# KHOI_NGUON.net
KiCad netlist of a schematic drawn in Altium Designer
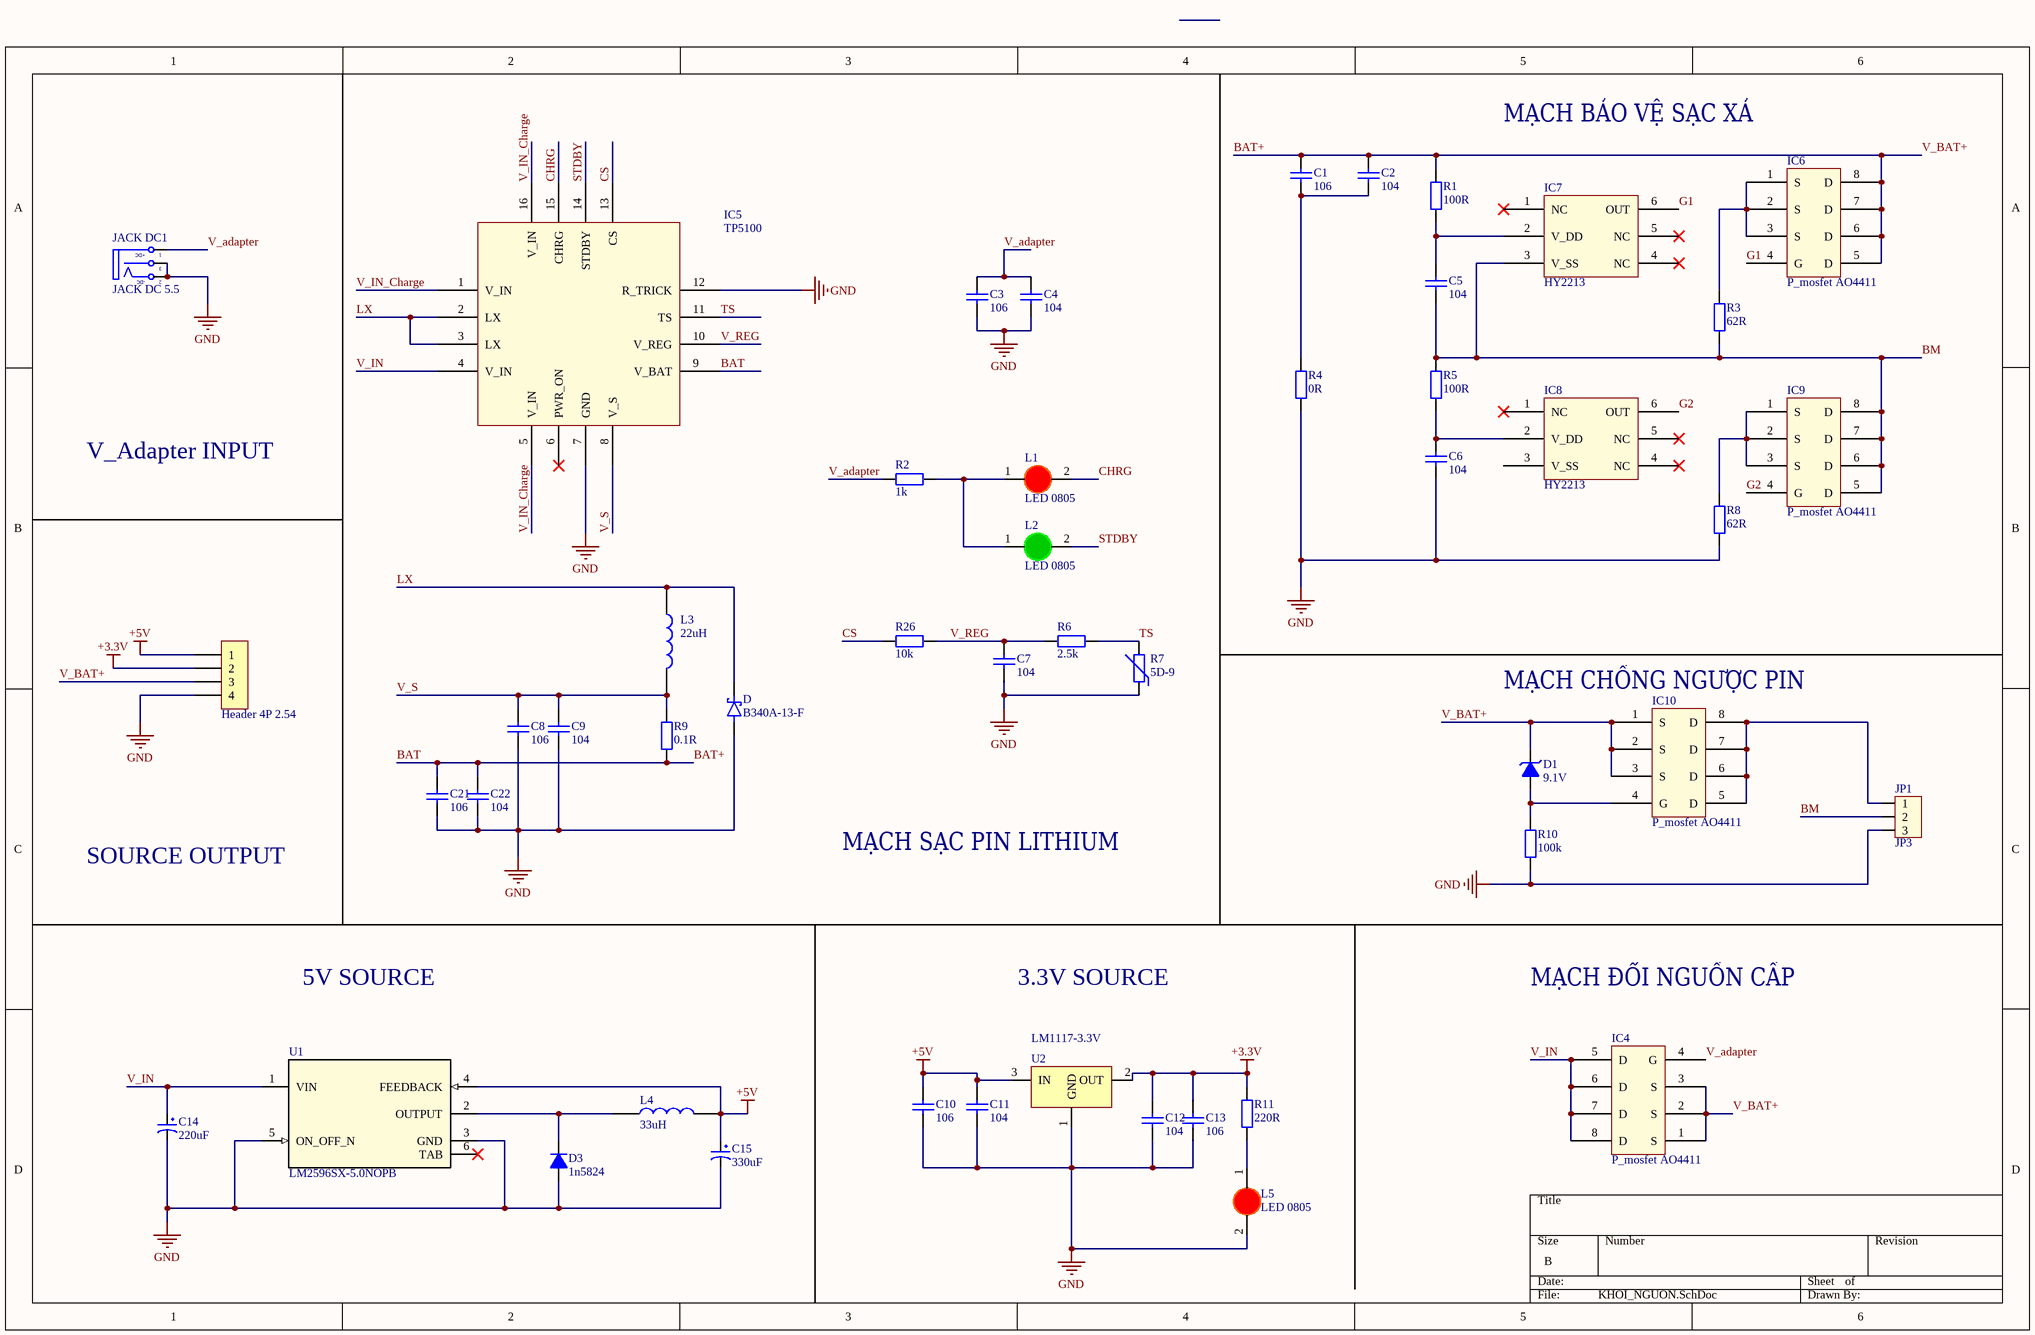
[diagram p0: KHOI_NGUON.SchDoc]

(export (version "E")
  (design (tool "Eeschema 10.0.6"))
  (components
    (comp (ref "C1")
      (value "106")
      (footprint "tu 1206")
      (description "Dán")
      (libsource (lib "Altium_Lib_by_KhueNguyenCreator") (part "Tu 1206 106 16V 20%"))
    )
    (comp (ref "C2")
      (value "104")
      (footprint "tu 1206")
      (description "Dán")
      (libsource (lib "Altium_Lib_by_KhueNguyenCreator") (part "Tu 1206 104 50V 20%"))
    )
    (comp (ref "C3")
      (value "106")
      (footprint "tu 1206")
      (description "Dán")
      (libsource (lib "Altium_Lib_by_KhueNguyenCreator") (part "Tu 1206 106 16V 20%"))
    )
    (comp (ref "C4")
      (value "104")
      (footprint "tu 1206")
      (description "Dán")
      (libsource (lib "Altium_Lib_by_KhueNguyenCreator") (part "Tu 1206 104 50V 20%"))
    )
    (comp (ref "C5")
      (value "104")
      (footprint "tu 1206")
      (description "Dán")
      (libsource (lib "Altium_Lib_by_KhueNguyenCreator") (part "Tu 1206 104 50V 20%"))
    )
    (comp (ref "C6")
      (value "104")
      (footprint "tu 1206")
      (description "Dán")
      (libsource (lib "Altium_Lib_by_KhueNguyenCreator") (part "Tu 1206 104 50V 20%"))
    )
    (comp (ref "C7")
      (value "104")
      (footprint "tu 1206")
      (description "Dán")
      (libsource (lib "Altium_Lib_by_KhueNguyenCreator") (part "Tu 1206 104 50V 20%"))
    )
    (comp (ref "C8")
      (value "106")
      (footprint "tu 1206")
      (description "Dán")
      (libsource (lib "Altium_Lib_by_KhueNguyenCreator") (part "Tu 1206 106 16V 20%"))
    )
    (comp (ref "C9")
      (value "104")
      (footprint "tu 1206")
      (description "Dán")
      (libsource (lib "Altium_Lib_by_KhueNguyenCreator") (part "Tu 1206 104 50V 20%"))
    )
    (comp (ref "C10")
      (value "106")
      (footprint "tu 1206")
      (description "Dán")
      (libsource (lib "Altium_Lib_by_KhueNguyenCreator") (part "Tu 1206 106 16V 20%"))
    )
    (comp (ref "C11")
      (value "104")
      (footprint "tu 1206")
      (description "Dán")
      (libsource (lib "Altium_Lib_by_KhueNguyenCreator") (part "Tu 1206 104 50V 20%"))
    )
    (comp (ref "C12")
      (value "104")
      (footprint "tu 1206")
      (description "Dán")
      (libsource (lib "Altium_Lib_by_KhueNguyenCreator") (part "Tu 1206 104 50V 20%"))
    )
    (comp (ref "C13")
      (value "106")
      (footprint "tu 1206")
      (description "Dán")
      (libsource (lib "Altium_Lib_by_KhueNguyenCreator") (part "Tu 1206 106 16V 20%"))
    )
    (comp (ref "C14")
      (value "220uF")
      (footprint "tu hoa 6.5mm")
      (description "Cắm")
      (libsource (lib "Altium_Lib_by_KhueNguyenCreator") (part "Tu Hoa 220uF 16V 7x11"))
    )
    (comp (ref "C15")
      (value "330uF")
      (footprint "tu hoa 10mm")
      (description "Cắm")
      (libsource (lib "Altium_Lib_by_KhueNguyenCreator") (part "Tu Hoa 330uF 35V 10x12"))
    )
    (comp (ref "C21")
      (value "106")
      (footprint "tu 1206")
      (description "Dán")
      (libsource (lib "Altium_Lib_by_KhueNguyenCreator") (part "Tu 1206 106 16V 20%"))
    )
    (comp (ref "C22")
      (value "104")
      (footprint "tu 1206")
      (description "Dán")
      (libsource (lib "Altium_Lib_by_KhueNguyenCreator") (part "Tu 1206 104 50V 20%"))
    )
    (comp (ref "D")
      (value "B340A-13-F")
      (footprint "DIOM5226X240N")
      (description "Diode Schottky 40V 3A Surface Mount SMA")
      (fields (field (name "MF") "Diodes Inc."))
      (libsource (lib "Altium_Lib_by_KhueNguyenCreator") (part "B340A-13-F"))
    )
    (comp (ref "D1")
      (value "9.1V")
      (footprint "DIODE ZENNER SMD SOD80")
      (description "Dán")
      (libsource (lib "Altium_Lib_by_KhueNguyenCreator") (part "Diode Zener 9.1V"))
    )
    (comp (ref "D3")
      (value "1n5824")
      (footprint "DIODE 1A")
      (description "Cắm")
      (libsource (lib "Altium_Lib_by_KhueNguyenCreator") (part "Diode 1N4007"))
    )
    (comp (ref "H1")
      (value "Header 4P 2.54")
      (footprint "XH2.54M-4")
      (description "Cắm")
      (libsource (lib "Altium_Lib_by_KhueNguyenCreator") (part "Header 4P 2.54 Duc Thang"))
    )
    (comp (ref "IC4")
      (value "P_mosfet AO4411")
      (footprint "SOIC8_AO4411")
      (libsource (lib "") (part "P_mosfet AO4411_1"))
    )
    (comp (ref "IC5")
      (value "TP5100")
      (footprint "QFN_16_4*4")
      (description "IC sạc pin Lithium")
      (libsource (lib "Schlib1") (part "TP5100"))
    )
    (comp (ref "IC6")
      (value "P_mosfet AO4411")
      (footprint "SOIC8_AO4411")
      (libsource (lib "AO4411") (part "P_mosfet AO4411"))
    )
    (comp (ref "IC7")
      (value "HY2213")
      (footprint "SOT_23_6_HY2213")
      (libsource (lib "HY22213") (part "HY2213"))
    )
    (comp (ref "IC8")
      (value "HY2213")
      (footprint "SOT_23_6_HY2213")
      (libsource (lib "HY22213") (part "HY2213"))
    )
    (comp (ref "IC9")
      (value "P_mosfet AO4411")
      (footprint "SOIC8_AO4411")
      (libsource (lib "AO4411") (part "P_mosfet AO4411"))
    )
    (comp (ref "IC10")
      (value "P_mosfet AO4411")
      (footprint "SOIC8_AO4411")
      (libsource (lib "AO4411") (part "P_mosfet AO4411"))
    )
    (comp (ref "JACK DC1")
      (value "JACK DC 5.5")
      (footprint "JACK DC 5.5")
      (libsource (lib "Altium_Lib_by_KhueNguyenCreator") (part "JACK DC 5.5"))
    )
    (comp (ref "JP1")
      (value "JP3")
      (footprint "CON3")
      (description "Connector 3")
      (libsource (lib "My library altium") (part "Con3"))
    )
    (comp (ref "L1")
      (value "LED 0805")
      (footprint "LED-1206-Red")
      (description "Dán")
      (libsource (lib "Altium_Lib_by_KhueNguyenCreator") (part "LED 1206 Do"))
    )
    (comp (ref "L2")
      (value "LED 0805")
      (footprint "LED-1206-Green")
      (description "Dán")
      (libsource (lib "Altium_Lib_by_KhueNguyenCreator") (part "LED 1206 Xanh La"))
    )
    (comp (ref "L3")
      (value "22uH")
      (footprint "Cuon Cam 12x12x10")
      (description "Dán")
      (libsource (lib "Altium_Lib_by_KhueNguyenCreator") (part "CUON CAM 100uH SMD"))
    )
    (comp (ref "L4")
      (value "33uH")
      (footprint "Cuon Cam 12x12x10")
      (description "Dán")
      (libsource (lib "") (part "CUON CAM 100uH SMD_1"))
    )
    (comp (ref "L5")
      (value "LED 0805")
      (footprint "LED-0805-Red")
      (description "Dán")
      (libsource (lib "Altium_Lib_by_KhueNguyenCreator") (part "LED 0805 Do"))
    )
    (comp (ref "R1")
      (value "100R")
      (footprint "tro smd 0805")
      (description "Dán")
      (libsource (lib "Altium_Lib_by_KhueNguyenCreator") (part "Tro 0805 1% 10R"))
    )
    (comp (ref "R2")
      (value "1k")
      (footprint "tro smd 0805")
      (description "Dán")
      (libsource (lib "Altium_Lib_by_KhueNguyenCreator") (part "Tro 0805 1% 1k"))
    )
    (comp (ref "R3")
      (value "62R")
      (footprint "tro smd 0805")
      (description "Dán")
      (libsource (lib "Altium_Lib_by_KhueNguyenCreator") (part "Tro 0805 5% 62R"))
    )
    (comp (ref "R4")
      (value "0R")
      (footprint "tro smd 0805")
      (description "Dán")
      (libsource (lib "Altium_Lib_by_KhueNguyenCreator") (part "Tro 0805 5% 0R"))
    )
    (comp (ref "R5")
      (value "100R")
      (footprint "tro smd 0805")
      (description "Dán")
      (libsource (lib "Altium_Lib_by_KhueNguyenCreator") (part "Tro 0805 1% 10R"))
    )
    (comp (ref "R6")
      (value "2.5k")
      (footprint "tro smd 0805")
      (description "Dán")
      (libsource (lib "Altium_Lib_by_KhueNguyenCreator") (part "Tro 0805 5% 2.7k"))
    )
    (comp (ref "R7")
      (value "5D-9")
      (footprint "tro nhiet d-9")
      (description "Cắm")
      (libsource (lib "Altium_Lib_by_KhueNguyenCreator") (part "Tro Nhiet NTC 5D-9"))
    )
    (comp (ref "R8")
      (value "62R")
      (footprint "tro smd 0805")
      (description "Dán")
      (libsource (lib "Altium_Lib_by_KhueNguyenCreator") (part "Tro 0805 5% 62R"))
    )
    (comp (ref "R9")
      (value "0.1R")
      (footprint "tro smd 2512")
      (description "Dán")
      (libsource (lib "Altium_Lib_by_KhueNguyenCreator") (part "Tro 2512 5% 0.1R"))
    )
    (comp (ref "R10")
      (value "100k")
      (footprint "tro smd 0805")
      (description "Dán")
      (libsource (lib "Altium_Lib_by_KhueNguyenCreator") (part "Tro 0805 5% 100k"))
    )
    (comp (ref "R11")
      (value "220R")
      (footprint "tro smd 0805")
      (description "Dán")
      (libsource (lib "Altium_Lib_by_KhueNguyenCreator") (part "Tro 0805 1% 0.5R"))
    )
    (comp (ref "R26")
      (value "10k")
      (footprint "tro smd 0805")
      (description "Dán")
      (libsource (lib "Altium_Lib_by_KhueNguyenCreator") (part "Tro 0805 1% 1k"))
    )
    (comp (ref "U1")
      (value "LM2596SX-5.0NOPB")
      (footprint "KTT0005B")
      (description "No Description Available")
      (fields
        (field (name "PARTNUMBER") "LM2596SX-ADJ/NOPB")
        (field (name "ALTERNATE_PARTNUMBER") "LM2596S-ADJ/NOPB")
      )
      (libsource (lib "LM2596SX-5P0NOPB") (part "LM2596SX-5.0NOPB"))
    )
    (comp (ref "U2")
      (value "LM1117-3.3V")
      (footprint "LM1117-SOP")
      (description "800mA Low-Dropout Linear Regulator")
      (fields (field (name "CREATOR") "Nguyen Ba Bien"))
      (libsource (lib "My library altium") (part "LM1117"))
    )
  )
  (nets
    (net (code "1") (name "+3.3V") (class "Default")
      (node (ref "C12") (pin "1") (pinfunction "1_1") (pintype "passive"))
      (node (ref "C13") (pin "2") (pinfunction "2_2") (pintype "passive"))
      (node (ref "H1") (pin "2") (pinfunction "2_2") (pintype "passive"))
      (node (ref "R11") (pin "1") (pinfunction "1_1") (pintype "passive"))
      (node (ref "U2") (pin "2") (pinfunction "OUT_2") (pintype "passive"))
    )
    (net (code "2") (name "+5V") (class "Default")
      (node (ref "C10") (pin "2") (pinfunction "2_2") (pintype "passive"))
      (node (ref "C11") (pin "1") (pinfunction "1_1") (pintype "passive"))
      (node (ref "C15") (pin "1") (pinfunction "1_1") (pintype "passive"))
      (node (ref "H1") (pin "1") (pinfunction "1_1") (pintype "passive"))
      (node (ref "L4") (pin "2") (pinfunction "2_2") (pintype "passive"))
      (node (ref "U1") (pin "4") (pinfunction "FEEDBACK_4") (pintype "input"))
      (node (ref "U2") (pin "3") (pinfunction "IN_3") (pintype "passive"))
    )
    (net (code "3") (name "/BAT") (class "Default")
      (node (ref "C1") (pin "2") (pinfunction "2_2") (pintype "passive"))
      (node (ref "C2") (pin "1") (pinfunction "1_1") (pintype "passive"))
      (node (ref "C21") (pin "2") (pinfunction "2_2") (pintype "passive"))
      (node (ref "C22") (pin "1") (pinfunction "1_1") (pintype "passive"))
      (node (ref "D1") (pin "2") (pinfunction "K_2") (pintype "passive"))
      (node (ref "H1") (pin "3") (pinfunction "3_3") (pintype "passive"))
      (node (ref "IC10") (pin "1") (pinfunction "S_1") (pintype "passive"))
      (node (ref "IC10") (pin "2") (pinfunction "S_2") (pintype "passive"))
      (node (ref "IC10") (pin "3") (pinfunction "S_3") (pintype "passive"))
      (node (ref "IC4") (pin "1") (pinfunction "S_1") (pintype "passive"))
      (node (ref "IC4") (pin "2") (pinfunction "S_2") (pintype "passive"))
      (node (ref "IC4") (pin "3") (pinfunction "S_3") (pintype "passive"))
      (node (ref "IC5") (pin "9") (pinfunction "V_BAT_9") (pintype "passive"))
      (node (ref "IC6") (pin "5") (pinfunction "D_5") (pintype "passive"))
      (node (ref "IC6") (pin "6") (pinfunction "D_6") (pintype "passive"))
      (node (ref "IC6") (pin "7") (pinfunction "D_7") (pintype "passive"))
      (node (ref "IC6") (pin "8") (pinfunction "D_8") (pintype "passive"))
      (node (ref "R1") (pin "2") (pinfunction "2_2") (pintype "passive"))
      (node (ref "R9") (pin "1") (pinfunction "1_1") (pintype "passive"))
    )
    (net (code "4") (name "/BM") (class "Default")
      (node (ref "C5") (pin "2") (pinfunction "2_2") (pintype "passive"))
      (node (ref "IC7") (pin "3") (pinfunction "V_SS_3") (pintype "passive"))
      (node (ref "IC9") (pin "5") (pinfunction "D_5") (pintype "passive"))
      (node (ref "IC9") (pin "6") (pinfunction "D_6") (pintype "passive"))
      (node (ref "IC9") (pin "7") (pinfunction "D_7") (pintype "passive"))
      (node (ref "IC9") (pin "8") (pinfunction "D_8") (pintype "passive"))
      (node (ref "JP1") (pin "2") (pinfunction "2_2") (pintype "passive"))
      (node (ref "R3") (pin "1") (pinfunction "1_1") (pintype "passive"))
      (node (ref "R5") (pin "2") (pinfunction "2_2") (pintype "passive"))
    )
    (net (code "5") (name "/CHRG") (class "Default")
      (node (ref "IC5") (pin "15") (pinfunction "CHRG_15") (pintype "passive"))
      (node (ref "L1") (pin "2") (pinfunction "K_2") (pintype "passive"))
    )
    (net (code "6") (name "/CS") (class "Default")
      (node (ref "IC5") (pin "13") (pinfunction "CS_13") (pintype "passive"))
      (node (ref "R26") (pin "2") (pinfunction "2_2") (pintype "passive"))
    )
    (net (code "7") (name "/G1") (class "Default")
      (node (ref "IC6") (pin "4") (pinfunction "G_4") (pintype "passive"))
      (node (ref "IC7") (pin "6") (pinfunction "OUT_6") (pintype "passive"))
    )
    (net (code "8") (name "/G2") (class "Default")
      (node (ref "IC8") (pin "6") (pinfunction "OUT_6") (pintype "passive"))
      (node (ref "IC9") (pin "4") (pinfunction "G_4") (pintype "passive"))
    )
    (net (code "9") (name "/LX") (class "Default")
      (node (ref "D") (pin "C") (pinfunction "C_C") (pintype "passive"))
      (node (ref "IC5") (pin "2") (pinfunction "LX_2") (pintype "passive"))
      (node (ref "IC5") (pin "3") (pinfunction "LX_3") (pintype "passive"))
      (node (ref "L3") (pin "1") (pinfunction "1_1") (pintype "passive"))
    )
    (net (code "10") (name "/STDBY") (class "Default")
      (node (ref "IC5") (pin "14") (pinfunction "STDBY_14") (pintype "passive"))
      (node (ref "L2") (pin "2") (pinfunction "K_2") (pintype "passive"))
    )
    (net (code "11") (name "/TS") (class "Default")
      (node (ref "IC5") (pin "11") (pinfunction "TS_11") (pintype "passive"))
      (node (ref "R6") (pin "2") (pinfunction "2_2") (pintype "passive"))
      (node (ref "R7") (pin "2") (pinfunction "2_2") (pintype "passive"))
    )
    (net (code "12") (name "/V_IN") (class "Default")
      (node (ref "C14") (pin "1") (pinfunction "1_1") (pintype "passive"))
      (node (ref "IC4") (pin "5") (pinfunction "D_5") (pintype "passive"))
      (node (ref "IC4") (pin "6") (pinfunction "D_6") (pintype "passive"))
      (node (ref "IC4") (pin "7") (pinfunction "D_7") (pintype "passive"))
      (node (ref "IC4") (pin "8") (pinfunction "D_8") (pintype "passive"))
      (node (ref "IC5") (pin "4") (pinfunction "V_IN_4") (pintype "passive"))
      (node (ref "U1") (pin "1") (pinfunction "VIN_1") (pintype "power_in"))
    )
    (net (code "13") (name "/V_IN_Charge") (class "Default")
      (node (ref "IC5") (pin "1") (pinfunction "V_IN_1") (pintype "passive"))
      (node (ref "IC5") (pin "16") (pinfunction "V_IN_16") (pintype "passive"))
      (node (ref "IC5") (pin "5") (pinfunction "V_IN_5") (pintype "passive"))
    )
    (net (code "14") (name "/V_REG") (class "Default")
      (node (ref "C7") (pin "1") (pinfunction "1_1") (pintype "passive"))
      (node (ref "IC5") (pin "10") (pinfunction "V_REG_10") (pintype "passive"))
      (node (ref "R26") (pin "1") (pinfunction "1_1") (pintype "passive"))
      (node (ref "R6") (pin "1") (pinfunction "1_1") (pintype "passive"))
    )
    (net (code "15") (name "/V_S") (class "Default")
      (node (ref "C8") (pin "2") (pinfunction "2_2") (pintype "passive"))
      (node (ref "C9") (pin "1") (pinfunction "1_1") (pintype "passive"))
      (node (ref "IC5") (pin "8") (pinfunction "V_S_8") (pintype "passive"))
      (node (ref "L3") (pin "2") (pinfunction "2_2") (pintype "passive"))
      (node (ref "R9") (pin "2") (pinfunction "2_2") (pintype "passive"))
    )
    (net (code "16") (name "/V_adapter") (class "Default")
      (node (ref "C3") (pin "2") (pinfunction "2_2") (pintype "passive"))
      (node (ref "C4") (pin "1") (pinfunction "1_1") (pintype "passive"))
      (node (ref "IC4") (pin "4") (pinfunction "G_4") (pintype "passive"))
      (node (ref "JACK DC1") (pin "1") (pinfunction "T_1") (pintype "passive"))
      (node (ref "R2") (pin "2") (pinfunction "2_2") (pintype "passive"))
    )
    (net (code "17") (name "GND") (class "Default")
      (node (ref "C10") (pin "1") (pinfunction "1_1") (pintype "passive"))
      (node (ref "C11") (pin "2") (pinfunction "2_2") (pintype "passive"))
      (node (ref "C12") (pin "2") (pinfunction "2_2") (pintype "passive"))
      (node (ref "C13") (pin "1") (pinfunction "1_1") (pintype "passive"))
      (node (ref "C14") (pin "2") (pinfunction "2_2") (pintype "passive"))
      (node (ref "C15") (pin "2") (pinfunction "2_2") (pintype "passive"))
      (node (ref "C21") (pin "1") (pinfunction "1_1") (pintype "passive"))
      (node (ref "C22") (pin "2") (pinfunction "2_2") (pintype "passive"))
      (node (ref "C3") (pin "1") (pinfunction "1_1") (pintype "passive"))
      (node (ref "C4") (pin "2") (pinfunction "2_2") (pintype "passive"))
      (node (ref "C6") (pin "2") (pinfunction "2_2") (pintype "passive"))
      (node (ref "C7") (pin "2") (pinfunction "2_2") (pintype "passive"))
      (node (ref "C8") (pin "1") (pinfunction "1_1") (pintype "passive"))
      (node (ref "C9") (pin "2") (pinfunction "2_2") (pintype "passive"))
      (node (ref "D") (pin "A") (pinfunction "A_A") (pintype "passive"))
      (node (ref "D3") (pin "1") (pinfunction "A_1") (pintype "passive"))
      (node (ref "H1") (pin "4") (pinfunction "4_4") (pintype "passive"))
      (node (ref "IC5") (pin "12") (pinfunction "R_TRICK_12") (pintype "passive"))
      (node (ref "IC5") (pin "7") (pinfunction "GND_7") (pintype "passive"))
      (node (ref "JACK DC1") (pin "2") (pinfunction "TN_2") (pintype "passive"))
      (node (ref "JACK DC1") (pin "3") (pinfunction "S_3") (pintype "power_in"))
      (node (ref "JP1") (pin "3") (pinfunction "3_3") (pintype "passive"))
      (node (ref "L5") (pin "2") (pinfunction "K_2") (pintype "passive"))
      (node (ref "R10") (pin "1") (pinfunction "1_1") (pintype "passive"))
      (node (ref "R4") (pin "1") (pinfunction "1_1") (pintype "passive"))
      (node (ref "R7") (pin "1") (pinfunction "1_1") (pintype "passive"))
      (node (ref "R8") (pin "1") (pinfunction "1_1") (pintype "passive"))
      (node (ref "U1") (pin "3") (pinfunction "GND_3") (pintype "power_in"))
      (node (ref "U1") (pin "5") (pinfunction "ON_OFF_N_5") (pintype "input"))
      (node (ref "U2") (pin "1") (pinfunction "GND_1") (pintype "passive"))
    )
    (net (code "18") (name "Net-(C1-Pad1)") (class "Default")
      (node (ref "C1") (pin "1") (pinfunction "1_1") (pintype "passive"))
      (node (ref "C2") (pin "2") (pinfunction "2_2") (pintype "passive"))
      (node (ref "R4") (pin "2") (pinfunction "2_2") (pintype "passive"))
    )
    (net (code "19") (name "Net-(D1-A)") (class "Default")
      (node (ref "D1") (pin "1") (pinfunction "A_1") (pintype "passive"))
      (node (ref "IC10") (pin "4") (pinfunction "G_4") (pintype "passive"))
      (node (ref "R10") (pin "2") (pinfunction "2_2") (pintype "passive"))
    )
    (net (code "20") (name "Net-(D3-K)") (class "Default")
      (node (ref "D3") (pin "2") (pinfunction "K_2") (pintype "passive"))
      (node (ref "L4") (pin "1") (pinfunction "1_1") (pintype "passive"))
      (node (ref "U1") (pin "2") (pinfunction "OUTPUT_2") (pintype "power_in"))
    )
    (net (code "21") (name "Net-(IC6-S-Pad1)") (class "Default")
      (node (ref "IC6") (pin "1") (pinfunction "S_1") (pintype "passive"))
      (node (ref "IC6") (pin "2") (pinfunction "S_2") (pintype "passive"))
      (node (ref "IC6") (pin "3") (pinfunction "S_3") (pintype "passive"))
      (node (ref "R3") (pin "2") (pinfunction "2_2") (pintype "passive"))
    )
    (net (code "22") (name "Net-(IC7-V_DD)") (class "Default")
      (node (ref "C5") (pin "1") (pinfunction "1_1") (pintype "passive"))
      (node (ref "IC7") (pin "2") (pinfunction "V_DD_2") (pintype "passive"))
      (node (ref "R1") (pin "1") (pinfunction "1_1") (pintype "passive"))
    )
    (net (code "23") (name "Net-(IC8-V_DD)") (class "Default")
      (node (ref "C6") (pin "1") (pinfunction "1_1") (pintype "passive"))
      (node (ref "IC8") (pin "2") (pinfunction "V_DD_2") (pintype "passive"))
      (node (ref "R5") (pin "1") (pinfunction "1_1") (pintype "passive"))
    )
    (net (code "24") (name "Net-(IC9-S-Pad1)") (class "Default")
      (node (ref "IC9") (pin "1") (pinfunction "S_1") (pintype "passive"))
      (node (ref "IC9") (pin "2") (pinfunction "S_2") (pintype "passive"))
      (node (ref "IC9") (pin "3") (pinfunction "S_3") (pintype "passive"))
      (node (ref "R8") (pin "2") (pinfunction "2_2") (pintype "passive"))
    )
    (net (code "25") (name "Net-(IC10-D-Pad5)") (class "Default")
      (node (ref "IC10") (pin "5") (pinfunction "D_5") (pintype "passive"))
      (node (ref "IC10") (pin "6") (pinfunction "D_6") (pintype "passive"))
      (node (ref "IC10") (pin "7") (pinfunction "D_7") (pintype "passive"))
      (node (ref "IC10") (pin "8") (pinfunction "D_8") (pintype "passive"))
      (node (ref "JP1") (pin "1") (pinfunction "1_1") (pintype "passive"))
    )
    (net (code "26") (name "Net-(L1-A)") (class "Default")
      (node (ref "L1") (pin "1") (pinfunction "A_1") (pintype "passive"))
      (node (ref "L2") (pin "1") (pinfunction "A_1") (pintype "passive"))
      (node (ref "R2") (pin "1") (pinfunction "1_1") (pintype "passive"))
    )
    (net (code "27") (name "Net-(L5-A)") (class "Default")
      (node (ref "L5") (pin "1") (pinfunction "A_1") (pintype "passive"))
      (node (ref "R11") (pin "2") (pinfunction "2_2") (pintype "passive"))
    )
    (net (code "28") (name "unconnected-(IC5-PWR_ON-Pad6)") (class "Default")
      (node (ref "IC5") (pin "6") (pinfunction "PWR_ON_6") (pintype "passive+no_connect"))
    )
    (net (code "29") (name "unconnected-(IC7-NC-Pad1)") (class "Default")
      (node (ref "IC7") (pin "1") (pinfunction "NC_1") (pintype "passive+no_connect"))
    )
    (net (code "30") (name "unconnected-(IC7-NC-Pad4)") (class "Default")
      (node (ref "IC7") (pin "4") (pinfunction "NC_4") (pintype "passive+no_connect"))
    )
    (net (code "31") (name "unconnected-(IC7-NC-Pad5)") (class "Default")
      (node (ref "IC7") (pin "5") (pinfunction "NC_5") (pintype "passive+no_connect"))
    )
    (net (code "32") (name "unconnected-(IC8-NC-Pad1)") (class "Default")
      (node (ref "IC8") (pin "1") (pinfunction "NC_1") (pintype "passive+no_connect"))
    )
    (net (code "33") (name "unconnected-(IC8-NC-Pad4)") (class "Default")
      (node (ref "IC8") (pin "4") (pinfunction "NC_4") (pintype "passive+no_connect"))
    )
    (net (code "34") (name "unconnected-(IC8-NC-Pad5)") (class "Default")
      (node (ref "IC8") (pin "5") (pinfunction "NC_5") (pintype "passive+no_connect"))
    )
    (net (code "35") (name "unconnected-(IC8-V_SS-Pad3)") (class "Default")
      (node (ref "IC8") (pin "3") (pinfunction "V_SS_3") (pintype "passive"))
    )
    (net (code "36") (name "unconnected-(U1-TAB-Pad6)") (class "Default")
      (node (ref "U1") (pin "6") (pinfunction "TAB_6") (pintype "power_in+no_connect"))
    )
  )
)
